# Arduino_MEGA_DRAM_Tester_2.net
KiCad netlist of a schematic drawn in EAGLE
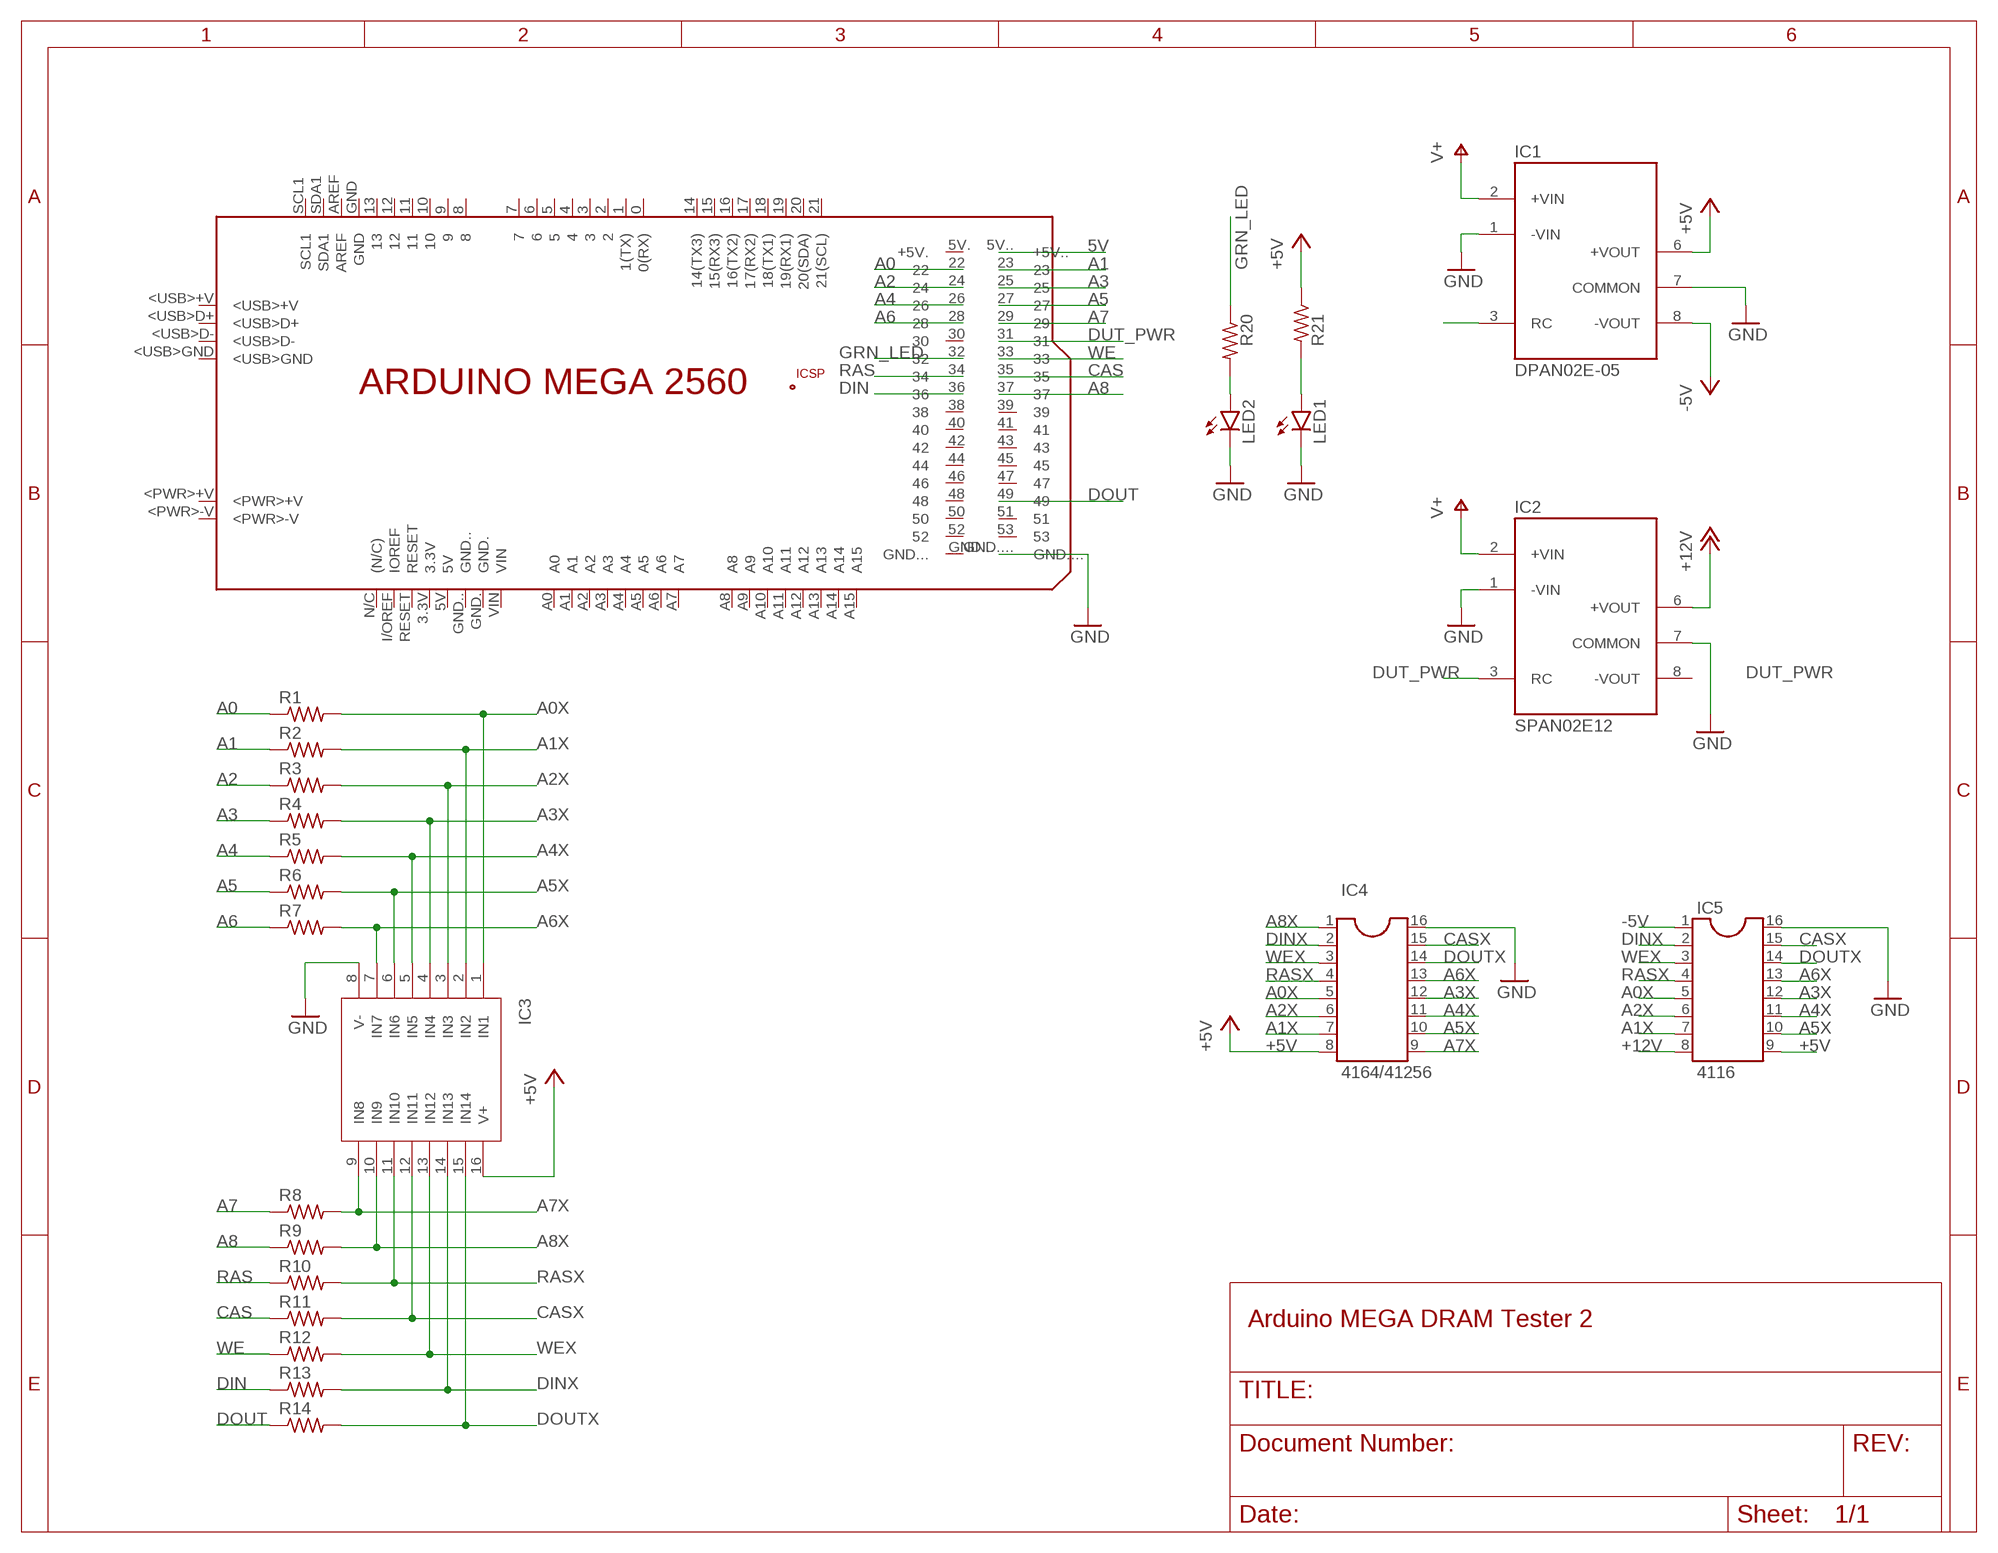
[diagram p0: schematic, sheet 1]

(export (version "E")
  (design (tool "Eeschema 10.0.6"))
  (components
    (comp (ref "IC1")
      (value "DPAN02E-05")
      (footprint "eagle-import:SIP7")
      (libsource (lib "eagle-import") (part "DPAN02"))
    )
    (comp (ref "IC2")
      (value "SPAN02E12")
      (footprint "eagle-import:SIP7")
      (libsource (lib "eagle-import") (part "DPAN02"))
    )
    (comp (ref "IC3")
      (value "SP720")
      (footprint "eagle-import:DIL16")
      (libsource (lib "eagle-import") (part "SP720"))
    )
    (comp (ref "IC4")
      (value "4164/41256")
      (footprint "eagle-import:DIL16")
      (libsource (lib "eagle-import") (part "DIL16"))
    )
    (comp (ref "IC5")
      (value "4116")
      (footprint "eagle-import:SOCKET-16")
      (libsource (lib "eagle-import") (part "DIL16S"))
    )
    (comp (ref "LED1")
      (value "LED5MM")
      (footprint "eagle-import:LED5MM")
      (libsource (lib "eagle-import") (part "LED5MM"))
    )
    (comp (ref "LED2")
      (value "LED5MM")
      (footprint "eagle-import:LED5MM")
      (libsource (lib "eagle-import") (part "LED5MM"))
    )
    (comp (ref "PCB1")
      (value "ARDUINO_MEGA2560")
      (footprint "eagle-import:ARDUINO_MEGA2560")
      (libsource (lib "eagle-import") (part "ARDUINO_MEGA2560"))
    )
    (comp (ref "R1")
      (value "R-US_V235/17")
      (footprint "eagle-import:V235_17")
      (libsource (lib "eagle-import") (part "R-US_V235/17"))
    )
    (comp (ref "R2")
      (value "R-US_V235/17")
      (footprint "eagle-import:V235_17")
      (libsource (lib "eagle-import") (part "R-US_V235/17"))
    )
    (comp (ref "R3")
      (value "R-US_V235/17")
      (footprint "eagle-import:V235_17")
      (libsource (lib "eagle-import") (part "R-US_V235/17"))
    )
    (comp (ref "R4")
      (value "R-US_V235/17")
      (footprint "eagle-import:V235_17")
      (libsource (lib "eagle-import") (part "R-US_V235/17"))
    )
    (comp (ref "R5")
      (value "R-US_V235/17")
      (footprint "eagle-import:V235_17")
      (libsource (lib "eagle-import") (part "R-US_V235/17"))
    )
    (comp (ref "R6")
      (value "R-US_V235/17")
      (footprint "eagle-import:V235_17")
      (libsource (lib "eagle-import") (part "R-US_V235/17"))
    )
    (comp (ref "R7")
      (value "R-US_V235/17")
      (footprint "eagle-import:V235_17")
      (libsource (lib "eagle-import") (part "R-US_V235/17"))
    )
    (comp (ref "R8")
      (value "R-US_V235/17")
      (footprint "eagle-import:V235_17")
      (libsource (lib "eagle-import") (part "R-US_V235/17"))
    )
    (comp (ref "R9")
      (value "R-US_V235/17")
      (footprint "eagle-import:V235_17")
      (libsource (lib "eagle-import") (part "R-US_V235/17"))
    )
    (comp (ref "R10")
      (value "R-US_V235/17")
      (footprint "eagle-import:V235_17")
      (libsource (lib "eagle-import") (part "R-US_V235/17"))
    )
    (comp (ref "R11")
      (value "R-US_V235/17")
      (footprint "eagle-import:V235_17")
      (libsource (lib "eagle-import") (part "R-US_V235/17"))
    )
    (comp (ref "R12")
      (value "R-US_V235/17")
      (footprint "eagle-import:V235_17")
      (libsource (lib "eagle-import") (part "R-US_V235/17"))
    )
    (comp (ref "R13")
      (value "R-US_V235/17")
      (footprint "eagle-import:V235_17")
      (libsource (lib "eagle-import") (part "R-US_V235/17"))
    )
    (comp (ref "R14")
      (value "R-US_V235/17")
      (footprint "eagle-import:V235_17")
      (libsource (lib "eagle-import") (part "R-US_V235/17"))
    )
    (comp (ref "R20")
      (value "R-US_0309/10")
      (footprint "eagle-import:0309_10")
      (libsource (lib "eagle-import") (part "resistor_348_R-US_0309/10"))
    )
    (comp (ref "R21")
      (value "R-US_0309/10")
      (footprint "eagle-import:0309_10")
      (libsource (lib "eagle-import") (part "resistor_348_R-US_0309/10"))
    )
  )
  (nets
    (net (code "1") (name "+5V") (class "Default")
      (node (ref "IC1") (pin "6") (pinfunction "+VOUT_6") (pintype "passive"))
      (node (ref "IC3") (pin "16") (pinfunction "V+_16") (pintype "input"))
      (node (ref "IC4") (pin "8") (pinfunction "8_8") (pintype "passive"))
      (node (ref "IC5") (pin "9") (pinfunction "9_9") (pintype "passive"))
      (node (ref "R21") (pin "1") (pinfunction "1_1") (pintype "passive"))
    )
    (net (code "2") (name "+12V") (class "Default")
      (node (ref "IC2") (pin "6") (pinfunction "+VOUT_6") (pintype "passive"))
      (node (ref "IC5") (pin "8") (pinfunction "8_8") (pintype "passive"))
    )
    (net (code "3") (name "-5V") (class "Default")
      (node (ref "IC1") (pin "8") (pinfunction "-VOUT_8") (pintype "passive"))
      (node (ref "IC5") (pin "1") (pinfunction "1_1") (pintype "passive"))
    )
    (net (code "4") (name "/5V") (class "Default")
      (node (ref "PCB1") (pin "5V..") (pinfunction "+5V.._5V..") (pintype "bidirectional"))
    )
    (net (code "5") (name "/A0") (class "Default")
      (node (ref "PCB1") (pin "22") (pinfunction "22_22") (pintype "bidirectional"))
      (node (ref "R1") (pin "1") (pinfunction "1_1") (pintype "passive"))
    )
    (net (code "6") (name "/A0X") (class "Default")
      (node (ref "IC3") (pin "1") (pinfunction "IN1_1") (pintype "input"))
      (node (ref "IC4") (pin "5") (pinfunction "5_5") (pintype "passive"))
      (node (ref "IC5") (pin "5") (pinfunction "5_5") (pintype "passive"))
      (node (ref "R1") (pin "2") (pinfunction "2_2") (pintype "passive"))
    )
    (net (code "7") (name "/A1") (class "Default")
      (node (ref "PCB1") (pin "23") (pinfunction "23_23") (pintype "bidirectional"))
      (node (ref "R2") (pin "1") (pinfunction "1_1") (pintype "passive"))
    )
    (net (code "8") (name "/A1X") (class "Default")
      (node (ref "IC3") (pin "2") (pinfunction "IN2_2") (pintype "input"))
      (node (ref "IC4") (pin "7") (pinfunction "7_7") (pintype "passive"))
      (node (ref "IC5") (pin "7") (pinfunction "7_7") (pintype "passive"))
      (node (ref "R2") (pin "2") (pinfunction "2_2") (pintype "passive"))
    )
    (net (code "9") (name "/A2") (class "Default")
      (node (ref "PCB1") (pin "24") (pinfunction "24_24") (pintype "bidirectional"))
      (node (ref "R3") (pin "1") (pinfunction "1_1") (pintype "passive"))
    )
    (net (code "10") (name "/A2X") (class "Default")
      (node (ref "IC3") (pin "3") (pinfunction "IN3_3") (pintype "input"))
      (node (ref "IC4") (pin "6") (pinfunction "6_6") (pintype "passive"))
      (node (ref "IC5") (pin "6") (pinfunction "6_6") (pintype "passive"))
      (node (ref "R3") (pin "2") (pinfunction "2_2") (pintype "passive"))
    )
    (net (code "11") (name "/A3") (class "Default")
      (node (ref "PCB1") (pin "25") (pinfunction "25_25") (pintype "bidirectional"))
      (node (ref "R4") (pin "1") (pinfunction "1_1") (pintype "passive"))
    )
    (net (code "12") (name "/A3X") (class "Default")
      (node (ref "IC3") (pin "4") (pinfunction "IN4_4") (pintype "input"))
      (node (ref "IC4") (pin "12") (pinfunction "12_12") (pintype "passive"))
      (node (ref "IC5") (pin "12") (pinfunction "12_12") (pintype "passive"))
      (node (ref "R4") (pin "2") (pinfunction "2_2") (pintype "passive"))
    )
    (net (code "13") (name "/A4") (class "Default")
      (node (ref "PCB1") (pin "26") (pinfunction "26_26") (pintype "bidirectional"))
      (node (ref "R5") (pin "1") (pinfunction "1_1") (pintype "passive"))
    )
    (net (code "14") (name "/A4X") (class "Default")
      (node (ref "IC3") (pin "5") (pinfunction "IN5_5") (pintype "input"))
      (node (ref "IC4") (pin "11") (pinfunction "11_11") (pintype "passive"))
      (node (ref "IC5") (pin "11") (pinfunction "11_11") (pintype "passive"))
      (node (ref "R5") (pin "2") (pinfunction "2_2") (pintype "passive"))
    )
    (net (code "15") (name "/A5") (class "Default")
      (node (ref "PCB1") (pin "27") (pinfunction "27_27") (pintype "bidirectional"))
      (node (ref "R6") (pin "1") (pinfunction "1_1") (pintype "passive"))
    )
    (net (code "16") (name "/A5X") (class "Default")
      (node (ref "IC3") (pin "6") (pinfunction "IN6_6") (pintype "input"))
      (node (ref "IC4") (pin "10") (pinfunction "10_10") (pintype "passive"))
      (node (ref "IC5") (pin "10") (pinfunction "10_10") (pintype "passive"))
      (node (ref "R6") (pin "2") (pinfunction "2_2") (pintype "passive"))
    )
    (net (code "17") (name "/A6") (class "Default")
      (node (ref "PCB1") (pin "28") (pinfunction "28_28") (pintype "bidirectional"))
      (node (ref "R7") (pin "1") (pinfunction "1_1") (pintype "passive"))
    )
    (net (code "18") (name "/A6X") (class "Default")
      (node (ref "IC3") (pin "7") (pinfunction "IN7_7") (pintype "input"))
      (node (ref "IC4") (pin "13") (pinfunction "13_13") (pintype "passive"))
      (node (ref "IC5") (pin "13") (pinfunction "13_13") (pintype "passive"))
      (node (ref "R7") (pin "2") (pinfunction "2_2") (pintype "passive"))
    )
    (net (code "19") (name "/A7") (class "Default")
      (node (ref "PCB1") (pin "29") (pinfunction "29_29") (pintype "bidirectional"))
      (node (ref "R8") (pin "1") (pinfunction "1_1") (pintype "passive"))
    )
    (net (code "20") (name "/A7X") (class "Default")
      (node (ref "IC3") (pin "9") (pinfunction "IN8_9") (pintype "input"))
      (node (ref "IC4") (pin "9") (pinfunction "9_9") (pintype "passive"))
      (node (ref "R8") (pin "2") (pinfunction "2_2") (pintype "passive"))
    )
    (net (code "21") (name "/A8") (class "Default")
      (node (ref "PCB1") (pin "37") (pinfunction "37_37") (pintype "bidirectional"))
      (node (ref "R9") (pin "1") (pinfunction "1_1") (pintype "passive"))
    )
    (net (code "22") (name "/A8X") (class "Default")
      (node (ref "IC3") (pin "10") (pinfunction "IN9_10") (pintype "input"))
      (node (ref "IC4") (pin "1") (pinfunction "1_1") (pintype "passive"))
      (node (ref "R9") (pin "2") (pinfunction "2_2") (pintype "passive"))
    )
    (net (code "23") (name "/CAS") (class "Default")
      (node (ref "PCB1") (pin "35") (pinfunction "35_35") (pintype "bidirectional"))
      (node (ref "R11") (pin "1") (pinfunction "1_1") (pintype "passive"))
    )
    (net (code "24") (name "/CASX") (class "Default")
      (node (ref "IC3") (pin "12") (pinfunction "IN11_12") (pintype "input"))
      (node (ref "IC4") (pin "15") (pinfunction "15_15") (pintype "passive"))
      (node (ref "IC5") (pin "15") (pinfunction "15_15") (pintype "passive"))
      (node (ref "R11") (pin "2") (pinfunction "2_2") (pintype "passive"))
    )
    (net (code "25") (name "/DIN") (class "Default")
      (node (ref "PCB1") (pin "36") (pinfunction "36_36") (pintype "bidirectional"))
      (node (ref "R13") (pin "1") (pinfunction "1_1") (pintype "passive"))
    )
    (net (code "26") (name "/DINX") (class "Default")
      (node (ref "IC3") (pin "14") (pinfunction "IN13_14") (pintype "input"))
      (node (ref "IC4") (pin "2") (pinfunction "2_2") (pintype "passive"))
      (node (ref "IC5") (pin "2") (pinfunction "2_2") (pintype "passive"))
      (node (ref "R13") (pin "2") (pinfunction "2_2") (pintype "passive"))
    )
    (net (code "27") (name "/DOUT") (class "Default")
      (node (ref "PCB1") (pin "49") (pinfunction "49_49") (pintype "bidirectional"))
      (node (ref "R14") (pin "1") (pinfunction "1_1") (pintype "passive"))
    )
    (net (code "28") (name "/DOUTX") (class "Default")
      (node (ref "IC3") (pin "15") (pinfunction "IN14_15") (pintype "input"))
      (node (ref "IC4") (pin "14") (pinfunction "14_14") (pintype "passive"))
      (node (ref "IC5") (pin "14") (pinfunction "14_14") (pintype "passive"))
      (node (ref "R14") (pin "2") (pinfunction "2_2") (pintype "passive"))
    )
    (net (code "29") (name "/DUT_PWR") (class "Default")
      (node (ref "IC1") (pin "3") (pinfunction "RC_3") (pintype "input"))
      (node (ref "IC2") (pin "3") (pinfunction "RC_3") (pintype "input"))
      (node (ref "PCB1") (pin "31") (pinfunction "31_31") (pintype "bidirectional"))
    )
    (net (code "30") (name "/GRN_LED") (class "Default")
      (node (ref "PCB1") (pin "32") (pinfunction "32_32") (pintype "bidirectional"))
      (node (ref "R20") (pin "1") (pinfunction "1_1") (pintype "passive"))
    )
    (net (code "31") (name "/RAS") (class "Default")
      (node (ref "PCB1") (pin "34") (pinfunction "34_34") (pintype "bidirectional"))
      (node (ref "R10") (pin "1") (pinfunction "1_1") (pintype "passive"))
    )
    (net (code "32") (name "/RASX") (class "Default")
      (node (ref "IC3") (pin "11") (pinfunction "IN10_11") (pintype "input"))
      (node (ref "IC4") (pin "4") (pinfunction "4_4") (pintype "passive"))
      (node (ref "IC5") (pin "4") (pinfunction "4_4") (pintype "passive"))
      (node (ref "R10") (pin "2") (pinfunction "2_2") (pintype "passive"))
    )
    (net (code "33") (name "/WE") (class "Default")
      (node (ref "PCB1") (pin "33") (pinfunction "33_33") (pintype "bidirectional"))
      (node (ref "R12") (pin "1") (pinfunction "1_1") (pintype "passive"))
    )
    (net (code "34") (name "/WEX") (class "Default")
      (node (ref "IC3") (pin "13") (pinfunction "IN12_13") (pintype "input"))
      (node (ref "IC4") (pin "3") (pinfunction "3_3") (pintype "passive"))
      (node (ref "IC5") (pin "3") (pinfunction "3_3") (pintype "passive"))
      (node (ref "R12") (pin "2") (pinfunction "2_2") (pintype "passive"))
    )
    (net (code "35") (name "GND") (class "Default")
      (node (ref "IC1") (pin "1") (pinfunction "-VIN_1") (pintype "input"))
      (node (ref "IC1") (pin "7") (pinfunction "COMMON_7") (pintype "passive"))
      (node (ref "IC2") (pin "1") (pinfunction "-VIN_1") (pintype "input"))
      (node (ref "IC2") (pin "7") (pinfunction "COMMON_7") (pintype "passive"))
      (node (ref "IC3") (pin "8") (pinfunction "V-_8") (pintype "input"))
      (node (ref "IC4") (pin "16") (pinfunction "16_16") (pintype "passive"))
      (node (ref "IC5") (pin "16") (pinfunction "16_16") (pintype "passive"))
      (node (ref "LED1") (pin "K") (pinfunction "C_K") (pintype "passive"))
      (node (ref "LED2") (pin "K") (pinfunction "C_K") (pintype "passive"))
      (node (ref "PCB1") (pin "GND....") (pinfunction "GND...._GND....") (pintype "bidirectional"))
    )
    (net (code "36") (name "Net-(LED1-PadA)") (class "Default")
      (node (ref "LED1") (pin "A") (pinfunction "A_A") (pintype "passive"))
      (node (ref "R21") (pin "2") (pinfunction "2_2") (pintype "passive"))
    )
    (net (code "37") (name "Net-(LED2-PadA)") (class "Default")
      (node (ref "LED2") (pin "A") (pinfunction "A_A") (pintype "passive"))
      (node (ref "R20") (pin "2") (pinfunction "2_2") (pintype "passive"))
    )
    (net (code "38") (name "V+") (class "Default")
      (node (ref "IC1") (pin "2") (pinfunction "+VIN_2") (pintype "input"))
      (node (ref "IC2") (pin "2") (pinfunction "+VIN_2") (pintype "input"))
    )
    (net (code "39") (name "unconnected-(IC2--VOUT-Pad8)") (class "Default")
      (node (ref "IC2") (pin "8") (pinfunction "-VOUT_8") (pintype "passive"))
    )
    (net (code "40") (name "unconnected-(PCB1-(N{slash}C)-PadN{slash}C)") (class "Default")
      (node (ref "PCB1") (pin "N/C") (pinfunction "(N/C)_N/C") (pintype "bidirectional"))
    )
    (net (code "41") (name "unconnected-(PCB1-+5V.-Pad5V.)") (class "Default")
      (node (ref "PCB1") (pin "5V.") (pinfunction "+5V._5V.") (pintype "bidirectional"))
    )
    (net (code "42") (name "unconnected-(PCB1-0(RX)-Pad0)") (class "Default")
      (node (ref "PCB1") (pin "0") (pinfunction "0(RX)_0") (pintype "bidirectional"))
    )
    (net (code "43") (name "unconnected-(PCB1-1(TX)-Pad1)") (class "Default")
      (node (ref "PCB1") (pin "1") (pinfunction "1(TX)_1") (pintype "bidirectional"))
    )
    (net (code "44") (name "unconnected-(PCB1-14(TX3)-Pad14)") (class "Default")
      (node (ref "PCB1") (pin "14") (pinfunction "14(TX3)_14") (pintype "bidirectional"))
    )
    (net (code "45") (name "unconnected-(PCB1-15(RX3)-Pad15)") (class "Default")
      (node (ref "PCB1") (pin "15") (pinfunction "15(RX3)_15") (pintype "bidirectional"))
    )
    (net (code "46") (name "unconnected-(PCB1-16(TX2)-Pad16)") (class "Default")
      (node (ref "PCB1") (pin "16") (pinfunction "16(TX2)_16") (pintype "bidirectional"))
    )
    (net (code "47") (name "unconnected-(PCB1-17(RX2)-Pad17)") (class "Default")
      (node (ref "PCB1") (pin "17") (pinfunction "17(RX2)_17") (pintype "bidirectional"))
    )
    (net (code "48") (name "unconnected-(PCB1-18(TX1)-Pad18)") (class "Default")
      (node (ref "PCB1") (pin "18") (pinfunction "18(TX1)_18") (pintype "bidirectional"))
    )
    (net (code "49") (name "unconnected-(PCB1-19(RX1)-Pad19)") (class "Default")
      (node (ref "PCB1") (pin "19") (pinfunction "19(RX1)_19") (pintype "bidirectional"))
    )
    (net (code "50") (name "unconnected-(PCB1-20(SDA)-Pad20)") (class "Default")
      (node (ref "PCB1") (pin "20") (pinfunction "20(SDA)_20") (pintype "bidirectional"))
    )
    (net (code "51") (name "unconnected-(PCB1-21(SCL)-Pad21)") (class "Default")
      (node (ref "PCB1") (pin "21") (pinfunction "21(SCL)_21") (pintype "bidirectional"))
    )
    (net (code "52") (name "unconnected-(PCB1-IOREF-PadI{slash}OREF)") (class "Default")
      (node (ref "PCB1") (pin "I/OREF") (pinfunction "IOREF_I/OREF") (pintype "bidirectional"))
    )
    (net (code "53") (name "unconnected-(PCB1-Pad+5V_)") (class "Default")
      (node (ref "PCB1") (pin "+5V_") (pinfunction "+5V__+5V_") (pintype "bidirectional"))
    )
    (net (code "54") (name "unconnected-(PCB1-Pad2)") (class "Default")
      (node (ref "PCB1") (pin "2") (pinfunction "2_2") (pintype "bidirectional"))
    )
    (net (code "55") (name "unconnected-(PCB1-Pad3)") (class "Default")
      (node (ref "PCB1") (pin "3") (pinfunction "3_3") (pintype "bidirectional"))
    )
    (net (code "56") (name "unconnected-(PCB1-Pad3.3V)") (class "Default")
      (node (ref "PCB1") (pin "3.3V") (pinfunction "3.3V_3.3V") (pintype "bidirectional"))
    )
    (net (code "57") (name "unconnected-(PCB1-Pad4)") (class "Default")
      (node (ref "PCB1") (pin "4") (pinfunction "4_4") (pintype "bidirectional"))
    )
    (net (code "58") (name "unconnected-(PCB1-Pad5)") (class "Default")
      (node (ref "PCB1") (pin "5") (pinfunction "5_5") (pintype "bidirectional"))
    )
    (net (code "59") (name "unconnected-(PCB1-Pad5V)") (class "Default")
      (node (ref "PCB1") (pin "5V") (pinfunction "5V_5V") (pintype "bidirectional"))
    )
    (net (code "60") (name "unconnected-(PCB1-Pad6)") (class "Default")
      (node (ref "PCB1") (pin "6") (pinfunction "6_6") (pintype "bidirectional"))
    )
    (net (code "61") (name "unconnected-(PCB1-Pad7)") (class "Default")
      (node (ref "PCB1") (pin "7") (pinfunction "7_7") (pintype "bidirectional"))
    )
    (net (code "62") (name "unconnected-(PCB1-Pad8)") (class "Default")
      (node (ref "PCB1") (pin "8") (pinfunction "8_8") (pintype "bidirectional"))
    )
    (net (code "63") (name "unconnected-(PCB1-Pad9)") (class "Default")
      (node (ref "PCB1") (pin "9") (pinfunction "9_9") (pintype "bidirectional"))
    )
    (net (code "64") (name "unconnected-(PCB1-Pad10)") (class "Default")
      (node (ref "PCB1") (pin "10") (pinfunction "10_10") (pintype "bidirectional"))
    )
    (net (code "65") (name "unconnected-(PCB1-Pad11)") (class "Default")
      (node (ref "PCB1") (pin "11") (pinfunction "11_11") (pintype "bidirectional"))
    )
    (net (code "66") (name "unconnected-(PCB1-Pad12)") (class "Default")
      (node (ref "PCB1") (pin "12") (pinfunction "12_12") (pintype "bidirectional"))
    )
    (net (code "67") (name "unconnected-(PCB1-Pad13)") (class "Default")
      (node (ref "PCB1") (pin "13") (pinfunction "13_13") (pintype "bidirectional"))
    )
    (net (code "68") (name "unconnected-(PCB1-Pad30)") (class "Default")
      (node (ref "PCB1") (pin "30") (pinfunction "30_30") (pintype "bidirectional"))
    )
    (net (code "69") (name "unconnected-(PCB1-Pad38)") (class "Default")
      (node (ref "PCB1") (pin "38") (pinfunction "38_38") (pintype "bidirectional"))
    )
    (net (code "70") (name "unconnected-(PCB1-Pad39)") (class "Default")
      (node (ref "PCB1") (pin "39") (pinfunction "39_39") (pintype "bidirectional"))
    )
    (net (code "71") (name "unconnected-(PCB1-Pad40)") (class "Default")
      (node (ref "PCB1") (pin "40") (pinfunction "40_40") (pintype "bidirectional"))
    )
    (net (code "72") (name "unconnected-(PCB1-Pad41)") (class "Default")
      (node (ref "PCB1") (pin "41") (pinfunction "41_41") (pintype "bidirectional"))
    )
    (net (code "73") (name "unconnected-(PCB1-Pad42)") (class "Default")
      (node (ref "PCB1") (pin "42") (pinfunction "42_42") (pintype "bidirectional"))
    )
    (net (code "74") (name "unconnected-(PCB1-Pad43)") (class "Default")
      (node (ref "PCB1") (pin "43") (pinfunction "43_43") (pintype "bidirectional"))
    )
    (net (code "75") (name "unconnected-(PCB1-Pad44)") (class "Default")
      (node (ref "PCB1") (pin "44") (pinfunction "44_44") (pintype "bidirectional"))
    )
    (net (code "76") (name "unconnected-(PCB1-Pad45)") (class "Default")
      (node (ref "PCB1") (pin "45") (pinfunction "45_45") (pintype "bidirectional"))
    )
    (net (code "77") (name "unconnected-(PCB1-Pad46)") (class "Default")
      (node (ref "PCB1") (pin "46") (pinfunction "46_46") (pintype "bidirectional"))
    )
    (net (code "78") (name "unconnected-(PCB1-Pad47)") (class "Default")
      (node (ref "PCB1") (pin "47") (pinfunction "47_47") (pintype "bidirectional"))
    )
    (net (code "79") (name "unconnected-(PCB1-Pad48)") (class "Default")
      (node (ref "PCB1") (pin "48") (pinfunction "48_48") (pintype "bidirectional"))
    )
    (net (code "80") (name "unconnected-(PCB1-Pad50)") (class "Default")
      (node (ref "PCB1") (pin "50") (pinfunction "50_50") (pintype "bidirectional"))
    )
    (net (code "81") (name "unconnected-(PCB1-Pad51)") (class "Default")
      (node (ref "PCB1") (pin "51") (pinfunction "51_51") (pintype "bidirectional"))
    )
    (net (code "82") (name "unconnected-(PCB1-Pad52)") (class "Default")
      (node (ref "PCB1") (pin "52") (pinfunction "52_52") (pintype "bidirectional"))
    )
    (net (code "83") (name "unconnected-(PCB1-Pad53)") (class "Default")
      (node (ref "PCB1") (pin "53") (pinfunction "53_53") (pintype "bidirectional"))
    )
    (net (code "84") (name "unconnected-(PCB1-Pad<PWR>+V)") (class "Default")
      (node (ref "PCB1") (pin "<PWR>+V") (pinfunction "<PWR>+V_<PWR>+V") (pintype "no_connect"))
    )
    (net (code "85") (name "unconnected-(PCB1-Pad<PWR>-V)") (class "Default")
      (node (ref "PCB1") (pin "<PWR>-V") (pinfunction "<PWR>-V_<PWR>-V") (pintype "no_connect"))
    )
    (net (code "86") (name "unconnected-(PCB1-Pad<USB>+V)") (class "Default")
      (node (ref "PCB1") (pin "<USB>+V") (pinfunction "<USB>+V_<USB>+V") (pintype "no_connect"))
    )
    (net (code "87") (name "unconnected-(PCB1-Pad<USB>D+)") (class "Default")
      (node (ref "PCB1") (pin "<USB>D+") (pinfunction "<USB>D+_<USB>D+") (pintype "no_connect"))
    )
    (net (code "88") (name "unconnected-(PCB1-Pad<USB>D-)") (class "Default")
      (node (ref "PCB1") (pin "<USB>D-") (pinfunction "<USB>D-_<USB>D-") (pintype "no_connect"))
    )
    (net (code "89") (name "unconnected-(PCB1-Pad<USB>GND)") (class "Default")
      (node (ref "PCB1") (pin "<USB>GND") (pinfunction "<USB>GND_<USB>GND") (pintype "no_connect"))
    )
    (net (code "90") (name "unconnected-(PCB1-PadA0)") (class "Default")
      (node (ref "PCB1") (pin "A0") (pinfunction "A0_A0") (pintype "bidirectional"))
    )
    (net (code "91") (name "unconnected-(PCB1-PadA1)") (class "Default")
      (node (ref "PCB1") (pin "A1") (pinfunction "A1_A1") (pintype "bidirectional"))
    )
    (net (code "92") (name "unconnected-(PCB1-PadA2)") (class "Default")
      (node (ref "PCB1") (pin "A2") (pinfunction "A2_A2") (pintype "bidirectional"))
    )
    (net (code "93") (name "unconnected-(PCB1-PadA3)") (class "Default")
      (node (ref "PCB1") (pin "A3") (pinfunction "A3_A3") (pintype "bidirectional"))
    )
    (net (code "94") (name "unconnected-(PCB1-PadA4)") (class "Default")
      (node (ref "PCB1") (pin "A4") (pinfunction "A4_A4") (pintype "bidirectional"))
    )
    (net (code "95") (name "unconnected-(PCB1-PadA5)") (class "Default")
      (node (ref "PCB1") (pin "A5") (pinfunction "A5_A5") (pintype "bidirectional"))
    )
    (net (code "96") (name "unconnected-(PCB1-PadA6)") (class "Default")
      (node (ref "PCB1") (pin "A6") (pinfunction "A6_A6") (pintype "bidirectional"))
    )
    (net (code "97") (name "unconnected-(PCB1-PadA7)") (class "Default")
      (node (ref "PCB1") (pin "A7") (pinfunction "A7_A7") (pintype "bidirectional"))
    )
    (net (code "98") (name "unconnected-(PCB1-PadA8)") (class "Default")
      (node (ref "PCB1") (pin "A8") (pinfunction "A8_A8") (pintype "bidirectional"))
    )
    (net (code "99") (name "unconnected-(PCB1-PadA9)") (class "Default")
      (node (ref "PCB1") (pin "A9") (pinfunction "A9_A9") (pintype "bidirectional"))
    )
    (net (code "100") (name "unconnected-(PCB1-PadA10)") (class "Default")
      (node (ref "PCB1") (pin "A10") (pinfunction "A10_A10") (pintype "bidirectional"))
    )
    (net (code "101") (name "unconnected-(PCB1-PadA11)") (class "Default")
      (node (ref "PCB1") (pin "A11") (pinfunction "A11_A11") (pintype "bidirectional"))
    )
    (net (code "102") (name "unconnected-(PCB1-PadA12)") (class "Default")
      (node (ref "PCB1") (pin "A12") (pinfunction "A12_A12") (pintype "bidirectional"))
    )
    (net (code "103") (name "unconnected-(PCB1-PadA13)") (class "Default")
      (node (ref "PCB1") (pin "A13") (pinfunction "A13_A13") (pintype "bidirectional"))
    )
    (net (code "104") (name "unconnected-(PCB1-PadA14)") (class "Default")
      (node (ref "PCB1") (pin "A14") (pinfunction "A14_A14") (pintype "bidirectional"))
    )
    (net (code "105") (name "unconnected-(PCB1-PadA15)") (class "Default")
      (node (ref "PCB1") (pin "A15") (pinfunction "A15_A15") (pintype "bidirectional"))
    )
    (net (code "106") (name "unconnected-(PCB1-PadAREF)") (class "Default")
      (node (ref "PCB1") (pin "AREF") (pinfunction "AREF_AREF") (pintype "bidirectional"))
    )
    (net (code "107") (name "unconnected-(PCB1-PadGND)") (class "Default")
      (node (ref "PCB1") (pin "GND") (pinfunction "GND_GND") (pintype "bidirectional"))
    )
    (net (code "108") (name "unconnected-(PCB1-PadGND.)") (class "Default")
      (node (ref "PCB1") (pin "GND.") (pinfunction "GND._GND.") (pintype "bidirectional"))
    )
    (net (code "109") (name "unconnected-(PCB1-PadGND..)") (class "Default")
      (node (ref "PCB1") (pin "GND..") (pinfunction "GND.._GND..") (pintype "bidirectional"))
    )
    (net (code "110") (name "unconnected-(PCB1-PadGND...)") (class "Default")
      (node (ref "PCB1") (pin "GND...") (pinfunction "GND..._GND...") (pintype "bidirectional"))
    )
    (net (code "111") (name "unconnected-(PCB1-PadGND__)") (class "Default")
      (node (ref "PCB1") (pin "GND__") (pinfunction "GND___GND__") (pintype "bidirectional"))
    )
    (net (code "112") (name "unconnected-(PCB1-PadMISO)") (class "Default")
      (node (ref "PCB1") (pin "MISO") (pinfunction "MISO_MISO") (pintype "bidirectional"))
    )
    (net (code "113") (name "unconnected-(PCB1-PadMOSI)") (class "Default")
      (node (ref "PCB1") (pin "MOSI") (pinfunction "MOSI_MOSI") (pintype "bidirectional"))
    )
    (net (code "114") (name "unconnected-(PCB1-PadRESET)") (class "Default")
      (node (ref "PCB1") (pin "RESET") (pinfunction "RESET_RESET") (pintype "bidirectional"))
    )
    (net (code "115") (name "unconnected-(PCB1-PadRESET.)") (class "Default")
      (node (ref "PCB1") (pin "RESET.") (pinfunction "RESET._RESET.") (pintype "bidirectional"))
    )
    (net (code "116") (name "unconnected-(PCB1-PadSCK)") (class "Default")
      (node (ref "PCB1") (pin "SCK") (pinfunction "SCK_SCK") (pintype "bidirectional"))
    )
    (net (code "117") (name "unconnected-(PCB1-PadSCL1)") (class "Default")
      (node (ref "PCB1") (pin "SCL1") (pinfunction "SCL1_SCL1") (pintype "bidirectional"))
    )
    (net (code "118") (name "unconnected-(PCB1-PadSDA1)") (class "Default")
      (node (ref "PCB1") (pin "SDA1") (pinfunction "SDA1_SDA1") (pintype "bidirectional"))
    )
    (net (code "119") (name "unconnected-(PCB1-PadVIN)") (class "Default")
      (node (ref "PCB1") (pin "VIN") (pinfunction "VIN_VIN") (pintype "bidirectional"))
    )
  )
)
